# CameraInterface.net
KiCad netlist of a schematic drawn in Altium Designer
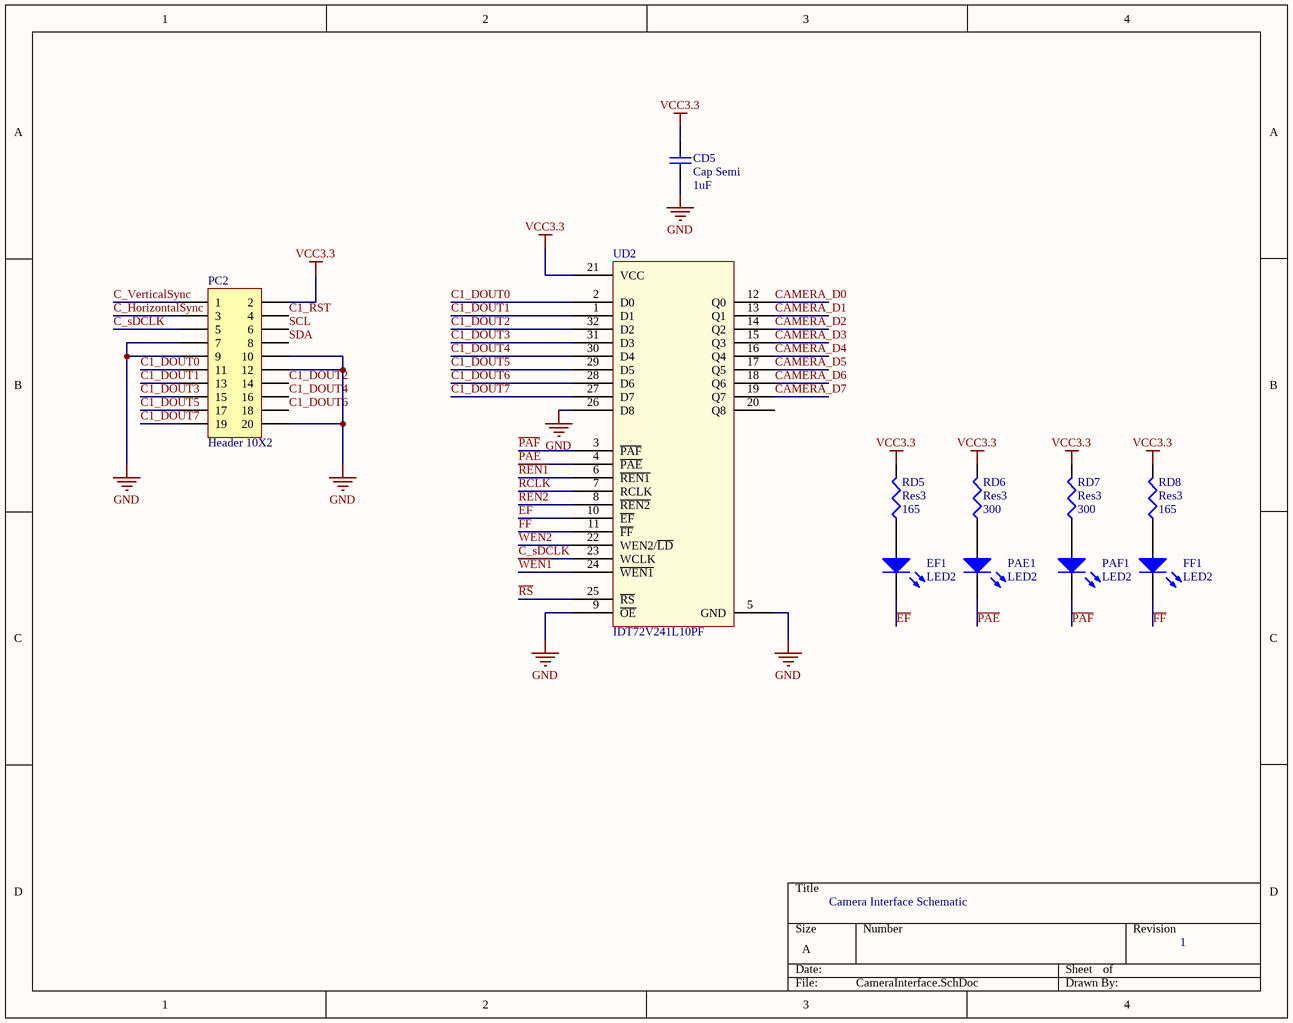
[diagram p0: CameraInterface.SchDoc]

(export (version "E")
  (design (tool "Eeschema 10.0.6"))
  (components
    (comp (ref "CD5")
      (value "Cap Semi")
      (footprint "CAPC1608L")
      (description "Capacitor (Semiconductor SIM Model)")
      (fields (field (name "ALTIUM_VALUE") "1uF") (field (name "PUBLISHER") "Altium Limited"))
      (libsource (lib "Miscellaneous Devices") (part "Cap Semi"))
    )
    (comp (ref "EF1")
      (value "LED2")
      (footprint "DIODE1608")
      (description "Typical RED, GREEN, YELLOW, AMBER GaAs LED")
      (fields (field (name "PUBLISHER") "Altium Limited"))
      (libsource (lib "Miscellaneous Devices") (part "LED2"))
    )
    (comp (ref "FF1")
      (value "LED2")
      (footprint "DIODE1608")
      (description "Typical RED, GREEN, YELLOW, AMBER GaAs LED")
      (fields (field (name "PUBLISHER") "Altium Limited"))
      (libsource (lib "Miscellaneous Devices") (part "LED2"))
    )
    (comp (ref "PAE1")
      (value "LED2")
      (footprint "DIODE1608")
      (description "Typical RED, GREEN, YELLOW, AMBER GaAs LED")
      (fields (field (name "PUBLISHER") "Altium Limited"))
      (libsource (lib "Miscellaneous Devices") (part "LED2"))
    )
    (comp (ref "PAF1")
      (value "LED2")
      (footprint "DIODE1608")
      (description "Typical RED, GREEN, YELLOW, AMBER GaAs LED")
      (fields (field (name "PUBLISHER") "Altium Limited"))
      (libsource (lib "Miscellaneous Devices") (part "LED2"))
    )
    (comp (ref "PC2")
      (value "Header 10X2")
      (footprint "HDR2X10")
      (description "Header, 10-Pin, Dual row")
      (fields (field (name "PUBLISHER") "Altium Limited"))
      (libsource (lib "Miscellaneous Connectors") (part "Header 10X2"))
    )
    (comp (ref "RD5")
      (value "Res3")
      (footprint "RESC1608L")
      (description "Resistor")
      (fields (field (name "ALTIUM_VALUE") "165") (field (name "PUBLISHER") "Altium Limited"))
      (libsource (lib "Miscellaneous Devices") (part "Res3"))
    )
    (comp (ref "RD6")
      (value "Res3")
      (footprint "RESC1608L")
      (description "Resistor")
      (fields (field (name "ALTIUM_VALUE") "300") (field (name "PUBLISHER") "Altium Limited"))
      (libsource (lib "Miscellaneous Devices") (part "Res3"))
    )
    (comp (ref "RD7")
      (value "Res3")
      (footprint "RESC1608L")
      (description "Resistor")
      (fields (field (name "ALTIUM_VALUE") "300") (field (name "PUBLISHER") "Altium Limited"))
      (libsource (lib "Miscellaneous Devices") (part "Res3"))
    )
    (comp (ref "RD8")
      (value "Res3")
      (footprint "RESC1608L")
      (description "Resistor")
      (fields (field (name "ALTIUM_VALUE") "165") (field (name "PUBLISHER") "Altium Limited"))
      (libsource (lib "Miscellaneous Devices") (part "Res3"))
    )
    (comp (ref "UD2")
      (value "IDT72V241L10PF")
      (footprint "IDT72V241L10PF")
      (description "36K (4K x 9) FIFO Buffer")
      (libsource (lib "daughterboard") (part "IDT72V241L10PF"))
    )
  )
  (nets
    (net (code "1") (name "/C1_DOUT0") (class "Default")
      (node (ref "PC2") (pin "11") (pinfunction "11_11") (pintype "passive"))
      (node (ref "UD2") (pin "2") (pinfunction "D0_2") (pintype "passive"))
    )
    (net (code "2") (name "/C1_DOUT1") (class "Default")
      (node (ref "PC2") (pin "13") (pinfunction "13_13") (pintype "passive"))
      (node (ref "UD2") (pin "1") (pinfunction "D1_1") (pintype "passive"))
    )
    (net (code "3") (name "/C1_DOUT2") (class "Default")
      (node (ref "PC2") (pin "14") (pinfunction "14_14") (pintype "passive"))
      (node (ref "UD2") (pin "32") (pinfunction "D2_32") (pintype "passive"))
    )
    (net (code "4") (name "/C1_DOUT3") (class "Default")
      (node (ref "PC2") (pin "15") (pinfunction "15_15") (pintype "passive"))
      (node (ref "UD2") (pin "31") (pinfunction "D3_31") (pintype "passive"))
    )
    (net (code "5") (name "/C1_DOUT4") (class "Default")
      (node (ref "PC2") (pin "16") (pinfunction "16_16") (pintype "passive"))
      (node (ref "UD2") (pin "30") (pinfunction "D4_30") (pintype "passive"))
    )
    (net (code "6") (name "/C1_DOUT5") (class "Default")
      (node (ref "PC2") (pin "17") (pinfunction "17_17") (pintype "passive"))
      (node (ref "UD2") (pin "29") (pinfunction "D5_29") (pintype "passive"))
    )
    (net (code "7") (name "/C1_DOUT6") (class "Default")
      (node (ref "PC2") (pin "18") (pinfunction "18_18") (pintype "passive"))
      (node (ref "UD2") (pin "28") (pinfunction "D6_28") (pintype "passive"))
    )
    (net (code "8") (name "/C1_DOUT7") (class "Default")
      (node (ref "PC2") (pin "19") (pinfunction "19_19") (pintype "passive"))
      (node (ref "UD2") (pin "27") (pinfunction "D7_27") (pintype "passive"))
    )
    (net (code "9") (name "/C1_RST") (class "Default")
      (node (ref "PC2") (pin "4") (pinfunction "4_4") (pintype "passive"))
    )
    (net (code "10") (name "/CAMERA_D0") (class "Default")
      (node (ref "UD2") (pin "12") (pinfunction "Q0_12") (pintype "passive"))
    )
    (net (code "11") (name "/CAMERA_D1") (class "Default")
      (node (ref "UD2") (pin "13") (pinfunction "Q1_13") (pintype "passive"))
    )
    (net (code "12") (name "/CAMERA_D2") (class "Default")
      (node (ref "UD2") (pin "14") (pinfunction "Q2_14") (pintype "passive"))
    )
    (net (code "13") (name "/CAMERA_D3") (class "Default")
      (node (ref "UD2") (pin "15") (pinfunction "Q3_15") (pintype "passive"))
    )
    (net (code "14") (name "/CAMERA_D4") (class "Default")
      (node (ref "UD2") (pin "16") (pinfunction "Q4_16") (pintype "passive"))
    )
    (net (code "15") (name "/CAMERA_D5") (class "Default")
      (node (ref "UD2") (pin "17") (pinfunction "Q5_17") (pintype "passive"))
    )
    (net (code "16") (name "/CAMERA_D6") (class "Default")
      (node (ref "UD2") (pin "18") (pinfunction "Q6_18") (pintype "passive"))
    )
    (net (code "17") (name "/CAMERA_D7") (class "Default")
      (node (ref "UD2") (pin "19") (pinfunction "Q7_19") (pintype "passive"))
    )
    (net (code "18") (name "/C_HorizontalSync") (class "Default")
      (node (ref "PC2") (pin "3") (pinfunction "3_3") (pintype "passive"))
    )
    (net (code "19") (name "/C_VerticalSync") (class "Default")
      (node (ref "PC2") (pin "1") (pinfunction "1_1") (pintype "passive"))
    )
    (net (code "20") (name "/C_sDCLK") (class "Default")
      (node (ref "PC2") (pin "5") (pinfunction "5_5") (pintype "passive"))
      (node (ref "UD2") (pin "23") (pinfunction "WCLK_23") (pintype "passive"))
    )
    (net (code "21") (name "/RCLK") (class "Default")
      (node (ref "UD2") (pin "7") (pinfunction "RCLK_7") (pintype "passive"))
    )
    (net (code "22") (name "/SCL") (class "Default")
      (node (ref "PC2") (pin "6") (pinfunction "6_6") (pintype "passive"))
    )
    (net (code "23") (name "/SDA") (class "Default")
      (node (ref "PC2") (pin "8") (pinfunction "8_8") (pintype "passive"))
    )
    (net (code "24") (name "/WEN2") (class "Default")
      (node (ref "UD2") (pin "22") (pinfunction "WEN2/~{LD}_22") (pintype "passive"))
    )
    (net (code "25") (name "/~{EF}") (class "Default")
      (node (ref "EF1") (pin "2") (pinfunction "K_2") (pintype "passive"))
      (node (ref "UD2") (pin "10") (pinfunction "~{EF}_10") (pintype "passive"))
    )
    (net (code "26") (name "/~{FF}") (class "Default")
      (node (ref "FF1") (pin "2") (pinfunction "K_2") (pintype "passive"))
      (node (ref "UD2") (pin "11") (pinfunction "~{FF}_11") (pintype "passive"))
    )
    (net (code "27") (name "/~{PAE}") (class "Default")
      (node (ref "PAE1") (pin "2") (pinfunction "K_2") (pintype "passive"))
      (node (ref "UD2") (pin "4") (pinfunction "~{PAE}_4") (pintype "passive"))
    )
    (net (code "28") (name "/~{PAF}") (class "Default")
      (node (ref "PAF1") (pin "2") (pinfunction "K_2") (pintype "passive"))
      (node (ref "UD2") (pin "3") (pinfunction "~{PAF}_3") (pintype "passive"))
    )
    (net (code "29") (name "/~{REN1}") (class "Default")
      (node (ref "UD2") (pin "6") (pinfunction "~{REN1}_6") (pintype "passive"))
    )
    (net (code "30") (name "/~{REN2}") (class "Default")
      (node (ref "UD2") (pin "8") (pinfunction "~{REN2}_8") (pintype "passive"))
    )
    (net (code "31") (name "/~{RS}") (class "Default")
      (node (ref "UD2") (pin "25") (pinfunction "~{RS}_25") (pintype "passive"))
    )
    (net (code "32") (name "/~{WEN1}") (class "Default")
      (node (ref "UD2") (pin "24") (pinfunction "~{WEN1}_24") (pintype "passive"))
    )
    (net (code "33") (name "GND") (class "Default")
      (node (ref "CD5") (pin "1") (pinfunction "1_1") (pintype "passive"))
      (node (ref "PC2") (pin "10") (pinfunction "10_10") (pintype "passive"))
      (node (ref "PC2") (pin "12") (pinfunction "12_12") (pintype "passive"))
      (node (ref "PC2") (pin "20") (pinfunction "20_20") (pintype "passive"))
      (node (ref "PC2") (pin "7") (pinfunction "7_7") (pintype "passive"))
      (node (ref "PC2") (pin "9") (pinfunction "9_9") (pintype "passive"))
      (node (ref "UD2") (pin "26") (pinfunction "D8_26") (pintype "passive"))
      (node (ref "UD2") (pin "5") (pinfunction "GND_5") (pintype "passive"))
      (node (ref "UD2") (pin "9") (pinfunction "~{OE}_9") (pintype "passive"))
    )
    (net (code "34") (name "Net-(EF1-A)") (class "Default")
      (node (ref "EF1") (pin "1") (pinfunction "A_1") (pintype "passive"))
      (node (ref "RD5") (pin "1") (pinfunction "1_1") (pintype "passive"))
    )
    (net (code "35") (name "Net-(FF1-A)") (class "Default")
      (node (ref "FF1") (pin "1") (pinfunction "A_1") (pintype "passive"))
      (node (ref "RD8") (pin "1") (pinfunction "1_1") (pintype "passive"))
    )
    (net (code "36") (name "Net-(PAE1-A)") (class "Default")
      (node (ref "PAE1") (pin "1") (pinfunction "A_1") (pintype "passive"))
      (node (ref "RD6") (pin "1") (pinfunction "1_1") (pintype "passive"))
    )
    (net (code "37") (name "Net-(PAF1-A)") (class "Default")
      (node (ref "PAF1") (pin "1") (pinfunction "A_1") (pintype "passive"))
      (node (ref "RD7") (pin "1") (pinfunction "1_1") (pintype "passive"))
    )
    (net (code "38") (name "VCC3.3") (class "Default")
      (node (ref "CD5") (pin "2") (pinfunction "2_2") (pintype "passive"))
      (node (ref "PC2") (pin "2") (pinfunction "2_2") (pintype "passive"))
      (node (ref "RD5") (pin "2") (pinfunction "2_2") (pintype "passive"))
      (node (ref "RD6") (pin "2") (pinfunction "2_2") (pintype "passive"))
      (node (ref "RD7") (pin "2") (pinfunction "2_2") (pintype "passive"))
      (node (ref "RD8") (pin "2") (pinfunction "2_2") (pintype "passive"))
      (node (ref "UD2") (pin "21") (pinfunction "VCC_21") (pintype "passive"))
    )
    (net (code "39") (name "unconnected-(UD2-Q8-Pad20)") (class "Default")
      (node (ref "UD2") (pin "20") (pinfunction "Q8_20") (pintype "passive"))
    )
  )
)
